# Pendant.net
KiCad netlist of a schematic drawn in EAGLE
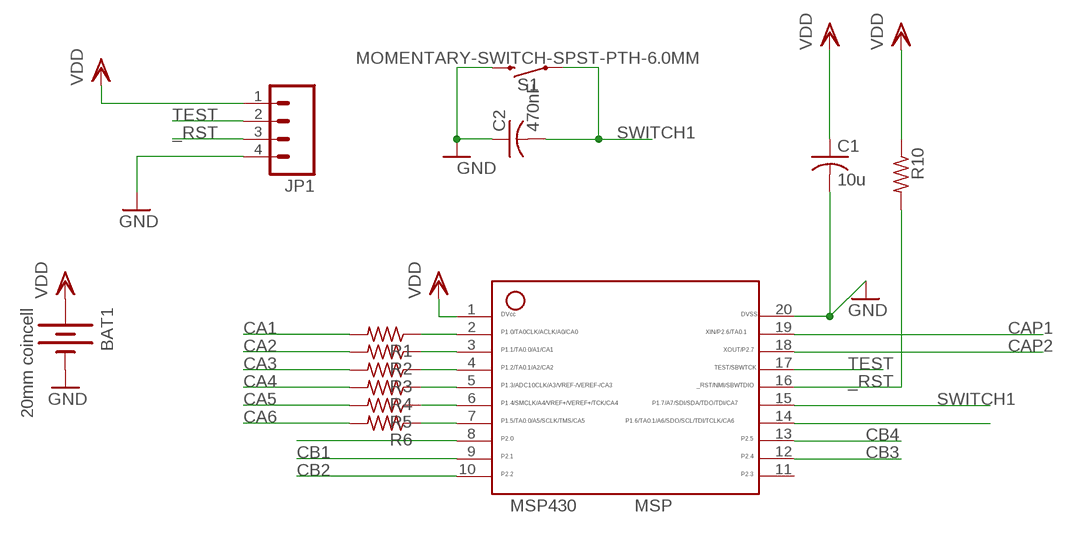
[diagram p0: schematic, sheet 1]
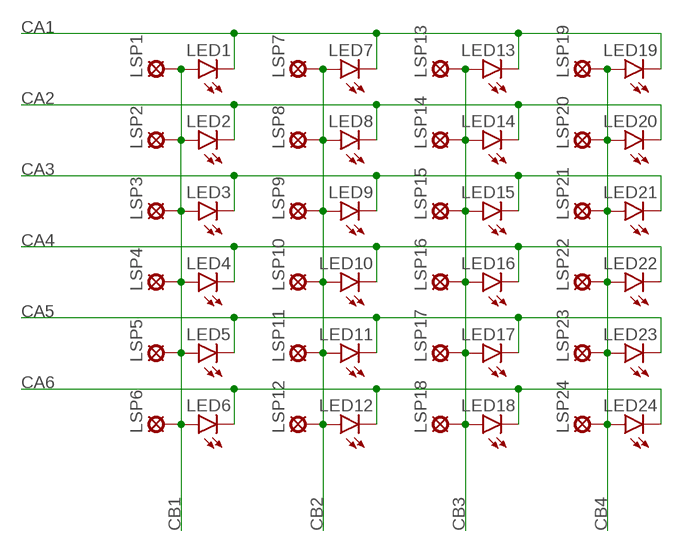
[diagram p1: schematic, sheet 2]

(export (version "E")
  (design (tool "Eeschema 10.0.6"))
  (components
    (comp (ref "BAT1")
      (value "20mm coincell")
      (footprint "eagle-import:BATTCON_20MM_PTH_COMPACT")
      (libsource (lib "eagle-import") (part "BATTERYFOB"))
    )
    (comp (ref "C1")
      (value "10u")
      (footprint "eagle-import:C1206")
      (libsource (lib "eagle-import") (part "C-USC1206"))
    )
    (comp (ref "C2")
      (value "470nF")
      (footprint "eagle-import:C1206")
      (libsource (lib "eagle-import") (part "C-USC1206"))
    )
    (comp (ref "JP1")
      (value "M04LOCK")
      (footprint "eagle-import:1X04_LOCK")
      (libsource (lib "eagle-import") (part "M04LOCK"))
    )
    (comp (ref "MSP430")
      (value "MSP")
      (footprint "eagle-import:20_PIN")
      (libsource (lib "eagle-import") (part "MSP430"))
    )
    (comp (ref "R1")
      (value "R-US_R1206")
      (footprint "eagle-import:R1206")
      (libsource (lib "eagle-import") (part "R-US_R1206"))
    )
    (comp (ref "R2")
      (value "R-US_R1206")
      (footprint "eagle-import:R1206")
      (libsource (lib "eagle-import") (part "R-US_R1206"))
    )
    (comp (ref "R3")
      (value "R-US_R1206")
      (footprint "eagle-import:R1206")
      (libsource (lib "eagle-import") (part "R-US_R1206"))
    )
    (comp (ref "R4")
      (value "R-US_R1206")
      (footprint "eagle-import:R1206")
      (libsource (lib "eagle-import") (part "R-US_R1206"))
    )
    (comp (ref "R5")
      (value "R-US_R1206")
      (footprint "eagle-import:R1206")
      (libsource (lib "eagle-import") (part "R-US_R1206"))
    )
    (comp (ref "R6")
      (value "R-US_R1206")
      (footprint "eagle-import:R1206")
      (libsource (lib "eagle-import") (part "R-US_R1206"))
    )
    (comp (ref "R10")
      (value "R-US_R1206")
      (footprint "eagle-import:R1206")
      (libsource (lib "eagle-import") (part "R-US_R1206"))
    )
    (comp (ref "S1")
      (value "MOMENTARY-SWITCH-SPST-PTH-6.0MM")
      (footprint "eagle-import:TACTILE_SWITCH_PTH_6.0MM")
      (libsource (lib "eagle-import") (part "MOMENTARY-SWITCH-SPST-PTH-6.0MM"))
    )
    (comp (ref "LED1")
      (value "LEDCHIPLED_1206")
      (footprint "eagle-import:CHIPLED_1206")
      (libsource (lib "eagle-import") (part "LEDCHIPLED_1206"))
    )
    (comp (ref "LED2")
      (value "LEDCHIPLED_1206")
      (footprint "eagle-import:CHIPLED_1206")
      (libsource (lib "eagle-import") (part "LEDCHIPLED_1206"))
    )
    (comp (ref "LED3")
      (value "LEDCHIPLED_1206")
      (footprint "eagle-import:CHIPLED_1206")
      (libsource (lib "eagle-import") (part "LEDCHIPLED_1206"))
    )
    (comp (ref "LED4")
      (value "LEDCHIPLED_1206")
      (footprint "eagle-import:CHIPLED_1206")
      (libsource (lib "eagle-import") (part "LEDCHIPLED_1206"))
    )
    (comp (ref "LED5")
      (value "LEDCHIPLED_1206")
      (footprint "eagle-import:CHIPLED_1206")
      (libsource (lib "eagle-import") (part "LEDCHIPLED_1206"))
    )
    (comp (ref "LED6")
      (value "LEDCHIPLED_1206")
      (footprint "eagle-import:CHIPLED_1206")
      (libsource (lib "eagle-import") (part "LEDCHIPLED_1206"))
    )
    (comp (ref "LED7")
      (value "LEDCHIPLED_1206")
      (footprint "eagle-import:CHIPLED_1206")
      (libsource (lib "eagle-import") (part "LEDCHIPLED_1206"))
    )
    (comp (ref "LED8")
      (value "LEDCHIPLED_1206")
      (footprint "eagle-import:CHIPLED_1206")
      (libsource (lib "eagle-import") (part "LEDCHIPLED_1206"))
    )
    (comp (ref "LED9")
      (value "LEDCHIPLED_1206")
      (footprint "eagle-import:CHIPLED_1206")
      (libsource (lib "eagle-import") (part "LEDCHIPLED_1206"))
    )
    (comp (ref "LED10")
      (value "LEDCHIPLED_1206")
      (footprint "eagle-import:CHIPLED_1206")
      (libsource (lib "eagle-import") (part "LEDCHIPLED_1206"))
    )
    (comp (ref "LED11")
      (value "LEDCHIPLED_1206")
      (footprint "eagle-import:CHIPLED_1206")
      (libsource (lib "eagle-import") (part "LEDCHIPLED_1206"))
    )
    (comp (ref "LED12")
      (value "LEDCHIPLED_1206")
      (footprint "eagle-import:CHIPLED_1206")
      (libsource (lib "eagle-import") (part "LEDCHIPLED_1206"))
    )
    (comp (ref "LED13")
      (value "LEDCHIPLED_1206")
      (footprint "eagle-import:CHIPLED_1206")
      (libsource (lib "eagle-import") (part "LEDCHIPLED_1206"))
    )
    (comp (ref "LED14")
      (value "LEDCHIPLED_1206")
      (footprint "eagle-import:CHIPLED_1206")
      (libsource (lib "eagle-import") (part "LEDCHIPLED_1206"))
    )
    (comp (ref "LED15")
      (value "LEDCHIPLED_1206")
      (footprint "eagle-import:CHIPLED_1206")
      (libsource (lib "eagle-import") (part "LEDCHIPLED_1206"))
    )
    (comp (ref "LED16")
      (value "LEDCHIPLED_1206")
      (footprint "eagle-import:CHIPLED_1206")
      (libsource (lib "eagle-import") (part "LEDCHIPLED_1206"))
    )
    (comp (ref "LED17")
      (value "LEDCHIPLED_1206")
      (footprint "eagle-import:CHIPLED_1206")
      (libsource (lib "eagle-import") (part "LEDCHIPLED_1206"))
    )
    (comp (ref "LED18")
      (value "LEDCHIPLED_1206")
      (footprint "eagle-import:CHIPLED_1206")
      (libsource (lib "eagle-import") (part "LEDCHIPLED_1206"))
    )
    (comp (ref "LED19")
      (value "LEDCHIPLED_1206")
      (footprint "eagle-import:CHIPLED_1206")
      (libsource (lib "eagle-import") (part "LEDCHIPLED_1206"))
    )
    (comp (ref "LED20")
      (value "LEDCHIPLED_1206")
      (footprint "eagle-import:CHIPLED_1206")
      (libsource (lib "eagle-import") (part "LEDCHIPLED_1206"))
    )
    (comp (ref "LED21")
      (value "LEDCHIPLED_1206")
      (footprint "eagle-import:CHIPLED_1206")
      (libsource (lib "eagle-import") (part "LEDCHIPLED_1206"))
    )
    (comp (ref "LED22")
      (value "LEDCHIPLED_1206")
      (footprint "eagle-import:CHIPLED_1206")
      (libsource (lib "eagle-import") (part "LEDCHIPLED_1206"))
    )
    (comp (ref "LED23")
      (value "LEDCHIPLED_1206")
      (footprint "eagle-import:CHIPLED_1206")
      (libsource (lib "eagle-import") (part "LEDCHIPLED_1206"))
    )
    (comp (ref "LED24")
      (value "LEDCHIPLED_1206")
      (footprint "eagle-import:CHIPLED_1206")
      (libsource (lib "eagle-import") (part "LEDCHIPLED_1206"))
    )
    (comp (ref "LSP1")
      (value "LSP10")
      (footprint "eagle-import:LSP10")
      (libsource (lib "eagle-import") (part "LSP10"))
    )
    (comp (ref "LSP2")
      (value "LSP10")
      (footprint "eagle-import:LSP10")
      (libsource (lib "eagle-import") (part "LSP10"))
    )
    (comp (ref "LSP3")
      (value "LSP10")
      (footprint "eagle-import:LSP10")
      (libsource (lib "eagle-import") (part "LSP10"))
    )
    (comp (ref "LSP4")
      (value "LSP10")
      (footprint "eagle-import:LSP10")
      (libsource (lib "eagle-import") (part "LSP10"))
    )
    (comp (ref "LSP5")
      (value "LSP10")
      (footprint "eagle-import:LSP10")
      (libsource (lib "eagle-import") (part "LSP10"))
    )
    (comp (ref "LSP6")
      (value "LSP10")
      (footprint "eagle-import:LSP10")
      (libsource (lib "eagle-import") (part "LSP10"))
    )
    (comp (ref "LSP7")
      (value "LSP10")
      (footprint "eagle-import:LSP10")
      (libsource (lib "eagle-import") (part "LSP10"))
    )
    (comp (ref "LSP8")
      (value "LSP10")
      (footprint "eagle-import:LSP10")
      (libsource (lib "eagle-import") (part "LSP10"))
    )
    (comp (ref "LSP9")
      (value "LSP10")
      (footprint "eagle-import:LSP10")
      (libsource (lib "eagle-import") (part "LSP10"))
    )
    (comp (ref "LSP10")
      (value "LSP10")
      (footprint "eagle-import:LSP10")
      (libsource (lib "eagle-import") (part "LSP10"))
    )
    (comp (ref "LSP11")
      (value "LSP10")
      (footprint "eagle-import:LSP10")
      (libsource (lib "eagle-import") (part "LSP10"))
    )
    (comp (ref "LSP12")
      (value "LSP10")
      (footprint "eagle-import:LSP10")
      (libsource (lib "eagle-import") (part "LSP10"))
    )
    (comp (ref "LSP13")
      (value "LSP10")
      (footprint "eagle-import:LSP10")
      (libsource (lib "eagle-import") (part "LSP10"))
    )
    (comp (ref "LSP14")
      (value "LSP10")
      (footprint "eagle-import:LSP10")
      (libsource (lib "eagle-import") (part "LSP10"))
    )
    (comp (ref "LSP15")
      (value "LSP10")
      (footprint "eagle-import:LSP10")
      (libsource (lib "eagle-import") (part "LSP10"))
    )
    (comp (ref "LSP16")
      (value "LSP10")
      (footprint "eagle-import:LSP10")
      (libsource (lib "eagle-import") (part "LSP10"))
    )
    (comp (ref "LSP17")
      (value "LSP10")
      (footprint "eagle-import:LSP10")
      (libsource (lib "eagle-import") (part "LSP10"))
    )
    (comp (ref "LSP18")
      (value "LSP10")
      (footprint "eagle-import:LSP10")
      (libsource (lib "eagle-import") (part "LSP10"))
    )
    (comp (ref "LSP19")
      (value "LSP10")
      (footprint "eagle-import:LSP10")
      (libsource (lib "eagle-import") (part "LSP10"))
    )
    (comp (ref "LSP20")
      (value "LSP10")
      (footprint "eagle-import:LSP10")
      (libsource (lib "eagle-import") (part "LSP10"))
    )
    (comp (ref "LSP21")
      (value "LSP10")
      (footprint "eagle-import:LSP10")
      (libsource (lib "eagle-import") (part "LSP10"))
    )
    (comp (ref "LSP22")
      (value "LSP10")
      (footprint "eagle-import:LSP10")
      (libsource (lib "eagle-import") (part "LSP10"))
    )
    (comp (ref "LSP23")
      (value "LSP10")
      (footprint "eagle-import:LSP10")
      (libsource (lib "eagle-import") (part "LSP10"))
    )
    (comp (ref "LSP24")
      (value "LSP10")
      (footprint "eagle-import:LSP10")
      (libsource (lib "eagle-import") (part "LSP10"))
    )
  )
  (nets
    (net (code "1") (name "CA1") (class "Default")
      (node (ref "LED1") (pin "C") (pinfunction "C_C") (pintype "passive"))
      (node (ref "LED13") (pin "C") (pinfunction "C_C") (pintype "passive"))
      (node (ref "LED19") (pin "C") (pinfunction "C_C") (pintype "passive"))
      (node (ref "LED7") (pin "C") (pinfunction "C_C") (pintype "passive"))
      (node (ref "R1") (pin "2") (pinfunction "2_2") (pintype "passive"))
    )
    (net (code "2") (name "CA2") (class "Default")
      (node (ref "LED14") (pin "C") (pinfunction "C_C") (pintype "passive"))
      (node (ref "LED2") (pin "C") (pinfunction "C_C") (pintype "passive"))
      (node (ref "LED20") (pin "C") (pinfunction "C_C") (pintype "passive"))
      (node (ref "LED8") (pin "C") (pinfunction "C_C") (pintype "passive"))
      (node (ref "R2") (pin "2") (pinfunction "2_2") (pintype "passive"))
    )
    (net (code "3") (name "CA3") (class "Default")
      (node (ref "LED15") (pin "C") (pinfunction "C_C") (pintype "passive"))
      (node (ref "LED21") (pin "C") (pinfunction "C_C") (pintype "passive"))
      (node (ref "LED3") (pin "C") (pinfunction "C_C") (pintype "passive"))
      (node (ref "LED9") (pin "C") (pinfunction "C_C") (pintype "passive"))
      (node (ref "R3") (pin "2") (pinfunction "2_2") (pintype "passive"))
    )
    (net (code "4") (name "CA4") (class "Default")
      (node (ref "LED10") (pin "C") (pinfunction "C_C") (pintype "passive"))
      (node (ref "LED16") (pin "C") (pinfunction "C_C") (pintype "passive"))
      (node (ref "LED22") (pin "C") (pinfunction "C_C") (pintype "passive"))
      (node (ref "LED4") (pin "C") (pinfunction "C_C") (pintype "passive"))
      (node (ref "R4") (pin "2") (pinfunction "2_2") (pintype "passive"))
    )
    (net (code "5") (name "CA5") (class "Default")
      (node (ref "LED11") (pin "C") (pinfunction "C_C") (pintype "passive"))
      (node (ref "LED17") (pin "C") (pinfunction "C_C") (pintype "passive"))
      (node (ref "LED23") (pin "C") (pinfunction "C_C") (pintype "passive"))
      (node (ref "LED5") (pin "C") (pinfunction "C_C") (pintype "passive"))
      (node (ref "R5") (pin "2") (pinfunction "2_2") (pintype "passive"))
    )
    (net (code "6") (name "CA6") (class "Default")
      (node (ref "LED12") (pin "C") (pinfunction "C_C") (pintype "passive"))
      (node (ref "LED18") (pin "C") (pinfunction "C_C") (pintype "passive"))
      (node (ref "LED24") (pin "C") (pinfunction "C_C") (pintype "passive"))
      (node (ref "LED6") (pin "C") (pinfunction "C_C") (pintype "passive"))
      (node (ref "R6") (pin "2") (pinfunction "2_2") (pintype "passive"))
    )
    (net (code "7") (name "CAP1") (class "Default")
      (node (ref "MSP430") (pin "19") (pinfunction "19_19") (pintype "bidirectional"))
    )
    (net (code "8") (name "CAP2") (class "Default")
      (node (ref "MSP430") (pin "18") (pinfunction "18_18") (pintype "bidirectional"))
    )
    (net (code "9") (name "CB1") (class "Default")
      (node (ref "LED1") (pin "A") (pinfunction "A_A") (pintype "passive"))
      (node (ref "LED2") (pin "A") (pinfunction "A_A") (pintype "passive"))
      (node (ref "LED3") (pin "A") (pinfunction "A_A") (pintype "passive"))
      (node (ref "LED4") (pin "A") (pinfunction "A_A") (pintype "passive"))
      (node (ref "LED5") (pin "A") (pinfunction "A_A") (pintype "passive"))
      (node (ref "LED6") (pin "A") (pinfunction "A_A") (pintype "passive"))
      (node (ref "LSP1") (pin "MP") (pinfunction "MP_MP") (pintype "passive"))
      (node (ref "LSP2") (pin "MP") (pinfunction "MP_MP") (pintype "passive"))
      (node (ref "LSP3") (pin "MP") (pinfunction "MP_MP") (pintype "passive"))
      (node (ref "LSP4") (pin "MP") (pinfunction "MP_MP") (pintype "passive"))
      (node (ref "LSP5") (pin "MP") (pinfunction "MP_MP") (pintype "passive"))
      (node (ref "LSP6") (pin "MP") (pinfunction "MP_MP") (pintype "passive"))
      (node (ref "MSP430") (pin "9") (pinfunction "9_9") (pintype "bidirectional"))
    )
    (net (code "10") (name "CB2") (class "Default")
      (node (ref "LED10") (pin "A") (pinfunction "A_A") (pintype "passive"))
      (node (ref "LED11") (pin "A") (pinfunction "A_A") (pintype "passive"))
      (node (ref "LED12") (pin "A") (pinfunction "A_A") (pintype "passive"))
      (node (ref "LED7") (pin "A") (pinfunction "A_A") (pintype "passive"))
      (node (ref "LED8") (pin "A") (pinfunction "A_A") (pintype "passive"))
      (node (ref "LED9") (pin "A") (pinfunction "A_A") (pintype "passive"))
      (node (ref "LSP10") (pin "MP") (pinfunction "MP_MP") (pintype "passive"))
      (node (ref "LSP11") (pin "MP") (pinfunction "MP_MP") (pintype "passive"))
      (node (ref "LSP12") (pin "MP") (pinfunction "MP_MP") (pintype "passive"))
      (node (ref "LSP7") (pin "MP") (pinfunction "MP_MP") (pintype "passive"))
      (node (ref "LSP8") (pin "MP") (pinfunction "MP_MP") (pintype "passive"))
      (node (ref "LSP9") (pin "MP") (pinfunction "MP_MP") (pintype "passive"))
      (node (ref "MSP430") (pin "10") (pinfunction "10_10") (pintype "bidirectional"))
    )
    (net (code "11") (name "CB3") (class "Default")
      (node (ref "LED13") (pin "A") (pinfunction "A_A") (pintype "passive"))
      (node (ref "LED14") (pin "A") (pinfunction "A_A") (pintype "passive"))
      (node (ref "LED15") (pin "A") (pinfunction "A_A") (pintype "passive"))
      (node (ref "LED16") (pin "A") (pinfunction "A_A") (pintype "passive"))
      (node (ref "LED17") (pin "A") (pinfunction "A_A") (pintype "passive"))
      (node (ref "LED18") (pin "A") (pinfunction "A_A") (pintype "passive"))
      (node (ref "LSP13") (pin "MP") (pinfunction "MP_MP") (pintype "passive"))
      (node (ref "LSP14") (pin "MP") (pinfunction "MP_MP") (pintype "passive"))
      (node (ref "LSP15") (pin "MP") (pinfunction "MP_MP") (pintype "passive"))
      (node (ref "LSP16") (pin "MP") (pinfunction "MP_MP") (pintype "passive"))
      (node (ref "LSP17") (pin "MP") (pinfunction "MP_MP") (pintype "passive"))
      (node (ref "LSP18") (pin "MP") (pinfunction "MP_MP") (pintype "passive"))
      (node (ref "MSP430") (pin "12") (pinfunction "12_12") (pintype "bidirectional"))
    )
    (net (code "12") (name "CB4") (class "Default")
      (node (ref "LED19") (pin "A") (pinfunction "A_A") (pintype "passive"))
      (node (ref "LED20") (pin "A") (pinfunction "A_A") (pintype "passive"))
      (node (ref "LED21") (pin "A") (pinfunction "A_A") (pintype "passive"))
      (node (ref "LED22") (pin "A") (pinfunction "A_A") (pintype "passive"))
      (node (ref "LED23") (pin "A") (pinfunction "A_A") (pintype "passive"))
      (node (ref "LED24") (pin "A") (pinfunction "A_A") (pintype "passive"))
      (node (ref "LSP19") (pin "MP") (pinfunction "MP_MP") (pintype "passive"))
      (node (ref "LSP20") (pin "MP") (pinfunction "MP_MP") (pintype "passive"))
      (node (ref "LSP21") (pin "MP") (pinfunction "MP_MP") (pintype "passive"))
      (node (ref "LSP22") (pin "MP") (pinfunction "MP_MP") (pintype "passive"))
      (node (ref "LSP23") (pin "MP") (pinfunction "MP_MP") (pintype "passive"))
      (node (ref "LSP24") (pin "MP") (pinfunction "MP_MP") (pintype "passive"))
      (node (ref "MSP430") (pin "13") (pinfunction "13_13") (pintype "bidirectional"))
    )
    (net (code "13") (name "GND") (class "Default")
      (node (ref "BAT1") (pin "2") (pinfunction "-_2") (pintype "power_in"))
      (node (ref "C1") (pin "2") (pinfunction "2_2") (pintype "passive"))
      (node (ref "C2") (pin "1") (pinfunction "1_1") (pintype "passive"))
      (node (ref "JP1") (pin "4") (pinfunction "4_4") (pintype "passive"))
      (node (ref "MSP430") (pin "20") (pinfunction "20_20") (pintype "bidirectional"))
      (node (ref "S1") (pin "3") (pinfunction "2_3") (pintype "passive"))
    )
    (net (code "14") (name "Net-(MSP430-Pad2)") (class "Default")
      (node (ref "MSP430") (pin "2") (pinfunction "2_2") (pintype "bidirectional"))
      (node (ref "R1") (pin "1") (pinfunction "1_1") (pintype "passive"))
    )
    (net (code "15") (name "Net-(MSP430-Pad3)") (class "Default")
      (node (ref "MSP430") (pin "3") (pinfunction "3_3") (pintype "bidirectional"))
      (node (ref "R2") (pin "1") (pinfunction "1_1") (pintype "passive"))
    )
    (net (code "16") (name "Net-(MSP430-Pad4)") (class "Default")
      (node (ref "MSP430") (pin "4") (pinfunction "4_4") (pintype "bidirectional"))
      (node (ref "R3") (pin "1") (pinfunction "1_1") (pintype "passive"))
    )
    (net (code "17") (name "Net-(MSP430-Pad5)") (class "Default")
      (node (ref "MSP430") (pin "5") (pinfunction "5_5") (pintype "bidirectional"))
      (node (ref "R4") (pin "1") (pinfunction "1_1") (pintype "passive"))
    )
    (net (code "18") (name "Net-(MSP430-Pad6)") (class "Default")
      (node (ref "MSP430") (pin "6") (pinfunction "6_6") (pintype "bidirectional"))
      (node (ref "R5") (pin "1") (pinfunction "1_1") (pintype "passive"))
    )
    (net (code "19") (name "Net-(MSP430-Pad7)") (class "Default")
      (node (ref "MSP430") (pin "7") (pinfunction "7_7") (pintype "bidirectional"))
      (node (ref "R6") (pin "1") (pinfunction "1_1") (pintype "passive"))
    )
    (net (code "20") (name "SWITCH1") (class "Default")
      (node (ref "C2") (pin "2") (pinfunction "2_2") (pintype "passive"))
      (node (ref "MSP430") (pin "15") (pinfunction "15_15") (pintype "bidirectional"))
      (node (ref "S1") (pin "1") (pinfunction "1_1") (pintype "passive"))
    )
    (net (code "21") (name "TEST") (class "Default")
      (node (ref "JP1") (pin "2") (pinfunction "2_2") (pintype "passive"))
      (node (ref "MSP430") (pin "17") (pinfunction "17_17") (pintype "bidirectional"))
    )
    (net (code "22") (name "VDD") (class "Default")
      (node (ref "BAT1") (pin "1") (pinfunction "+_1") (pintype "power_in"))
      (node (ref "BAT1") (pin "3") (pinfunction "+_3") (pintype "power_in"))
      (node (ref "BAT1") (pin "4") (pinfunction "+_4") (pintype "power_in"))
      (node (ref "BAT1") (pin "5") (pinfunction "+_5") (pintype "power_in"))
      (node (ref "C1") (pin "1") (pinfunction "1_1") (pintype "passive"))
      (node (ref "JP1") (pin "1") (pinfunction "1_1") (pintype "passive"))
      (node (ref "MSP430") (pin "1") (pinfunction "1_1") (pintype "bidirectional"))
      (node (ref "R10") (pin "1") (pinfunction "1_1") (pintype "passive"))
    )
    (net (code "23") (name "_RST") (class "Default")
      (node (ref "JP1") (pin "3") (pinfunction "3_3") (pintype "passive"))
      (node (ref "MSP430") (pin "16") (pinfunction "16_16") (pintype "bidirectional"))
      (node (ref "R10") (pin "2") (pinfunction "2_2") (pintype "passive"))
    )
    (net (code "24") (name "unconnected-(MSP430-Pad8)") (class "Default")
      (node (ref "MSP430") (pin "8") (pinfunction "8_8") (pintype "bidirectional"))
    )
    (net (code "25") (name "unconnected-(MSP430-Pad11)") (class "Default")
      (node (ref "MSP430") (pin "11") (pinfunction "11_11") (pintype "bidirectional"))
    )
    (net (code "26") (name "unconnected-(MSP430-Pad14)") (class "Default")
      (node (ref "MSP430") (pin "14") (pinfunction "14_14") (pintype "bidirectional"))
    )
  )
)
